# Power.net
KiCad netlist of a schematic drawn in Altium Designer
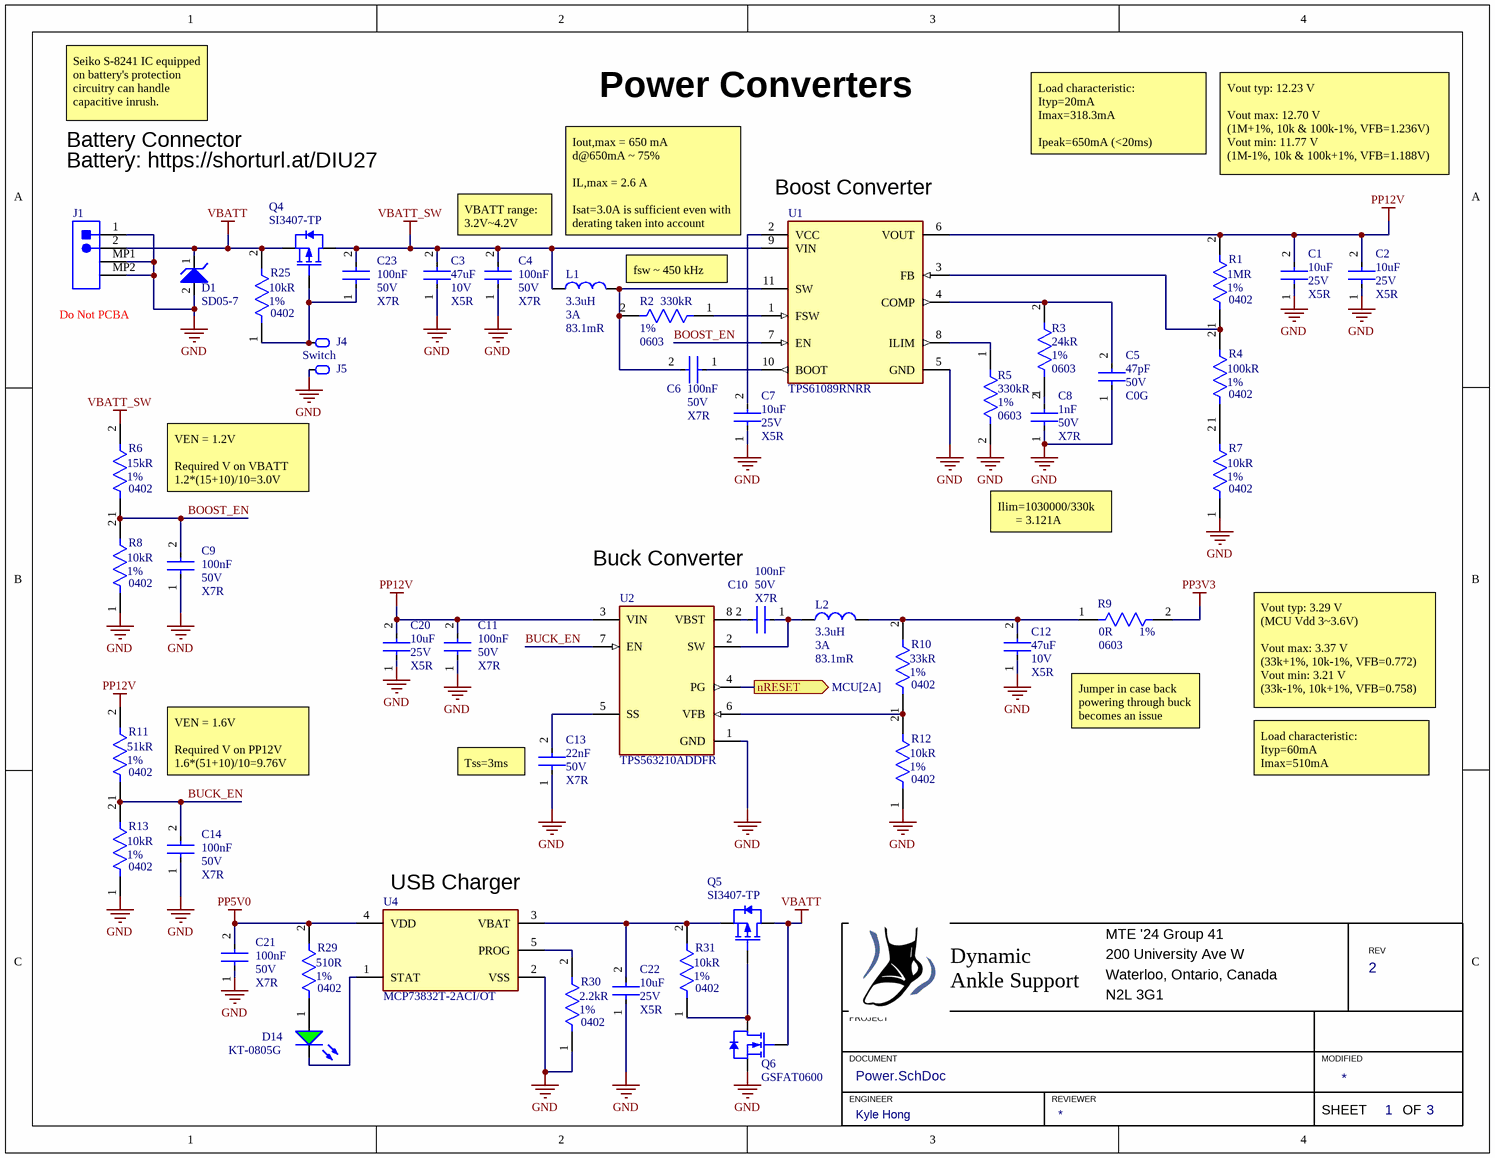
[diagram p0: Power.SchDoc]

(export (version "E")
  (design (tool "Eeschema 10.0.6"))
  (components
    (comp (ref "C1")
      (value "CL21A106KAYNNNE")
      (footprint "CAP0805")
      (description "25V 10uF X5R ±10% 0805  Multilayer Ceramic Capacitors MLCC - SMD/SMT ROHS")
      (fields
        (field (name "TOLERANCE") "10%")
        (field (name "MANUFACTURER") "Samsung Electro-Mechanics")
        (field (name "DIELECTRIC") "X5R")
        (field (name "VOLTAGE RATING") "25V")
        (field (name "CAPACITANCE") "10uF")
      )
      (libsource (lib "FYDP_library_sch") (part "CAP0805"))
    )
    (comp (ref "C2")
      (value "CL21A106KAYNNNE")
      (footprint "CAP0805")
      (description "25V 10uF X5R ±10% 0805  Multilayer Ceramic Capacitors MLCC - SMD/SMT ROHS")
      (fields
        (field (name "TOLERANCE") "10%")
        (field (name "MANUFACTURER") "Samsung Electro-Mechanics")
        (field (name "DIELECTRIC") "X5R")
        (field (name "VOLTAGE RATING") "25V")
        (field (name "CAPACITANCE") "10uF")
      )
      (libsource (lib "FYDP_library_sch") (part "CAP0805"))
    )
    (comp (ref "C3")
      (value "CL31A476MPHNNNE")
      (footprint "CAP1206")
      (description "10V 47uF X5R ±20% 1206  Multilayer Ceramic Capacitors MLCC - SMD/SMT ROHS")
      (fields
        (field (name "TOLERANCE") "20%")
        (field (name "MANUFACTURER") "Samsung Electro-Mechanics")
        (field (name "DIELECTRIC") "X5R")
        (field (name "VOLTAGE RATING") "10V")
        (field (name "CAPACITANCE") "47uF")
      )
      (libsource (lib "FYDP_library_sch") (part "CAP1206"))
    )
    (comp (ref "C4")
      (value "CL05B104KB54PNC")
      (footprint "CAP0402")
      (description "50V 100nF X7R ±10% 0402  Multilayer Ceramic Capacitors MLCC - SMD/SMT ROHS")
      (fields
        (field (name "TOLERANCE") "±20%")
        (field (name "MANUFACTURER") "Samsung Electro-Mechanics")
        (field (name "DIELECTRIC") "X7R")
        (field (name "VOLTAGE RATING") "50V")
        (field (name "CAPACITANCE") "100nF")
      )
      (libsource (lib "FYDP_library_sch") (part "CAP0402"))
    )
    (comp (ref "C5")
      (value "0402CG470J500NT")
      (footprint "CAP0402")
      (description "50V 47pF C0G ±5% 0402  Multilayer Ceramic Capacitors MLCC - SMD/SMT ROHS")
      (fields
        (field (name "TOLERANCE") "±5%")
        (field (name "MANUFACTURER") "FH (Guangdong Fenghua Advanced Tech)")
        (field (name "DIELECTRIC") "C0G")
        (field (name "VOLTAGE RATING") "50V")
        (field (name "CAPACITANCE") "47pF")
      )
      (libsource (lib "FYDP_library_sch") (part "CAP0402"))
    )
    (comp (ref "C6")
      (value "CL05B104KB54PNC")
      (footprint "CAP0402")
      (description "50V 100nF X7R ±10% 0402  Multilayer Ceramic Capacitors MLCC - SMD/SMT ROHS")
      (fields
        (field (name "TOLERANCE") "±20%")
        (field (name "MANUFACTURER") "Samsung Electro-Mechanics")
        (field (name "DIELECTRIC") "X7R")
        (field (name "VOLTAGE RATING") "50V")
        (field (name "CAPACITANCE") "100nF")
      )
      (libsource (lib "FYDP_library_sch") (part "CAP0402"))
    )
    (comp (ref "C7")
      (value "CL21A106KAYNNNE")
      (footprint "CAP0805")
      (description "25V 10uF X5R ±10% 0805  Multilayer Ceramic Capacitors MLCC - SMD/SMT ROHS")
      (fields
        (field (name "TOLERANCE") "10%")
        (field (name "MANUFACTURER") "Samsung Electro-Mechanics")
        (field (name "DIELECTRIC") "X5R")
        (field (name "VOLTAGE RATING") "25V")
        (field (name "CAPACITANCE") "10uF")
      )
      (libsource (lib "FYDP_library_sch") (part "CAP0805"))
    )
    (comp (ref "C8")
      (value "0402B102K500NT")
      (footprint "CAP0402")
      (description "50V 1nF X7R ±10% 0402  Multilayer Ceramic Capacitors MLCC - SMD/SMT ROHS")
      (fields
        (field (name "TOLERANCE") "±10%")
        (field (name "MANUFACTURER") "FH (Guangdong Fenghua Advanced Tech)")
        (field (name "DIELECTRIC") "X7R")
        (field (name "VOLTAGE RATING") "50V")
        (field (name "CAPACITANCE") "1nF")
      )
      (libsource (lib "FYDP_library_sch") (part "CAP0402"))
    )
    (comp (ref "C9")
      (value "CL05B104KB54PNC")
      (footprint "CAP0402")
      (description "50V 100nF X7R ±10% 0402  Multilayer Ceramic Capacitors MLCC - SMD/SMT ROHS")
      (fields
        (field (name "TOLERANCE") "±20%")
        (field (name "MANUFACTURER") "Samsung Electro-Mechanics")
        (field (name "DIELECTRIC") "X7R")
        (field (name "VOLTAGE RATING") "50V")
        (field (name "CAPACITANCE") "100nF")
      )
      (libsource (lib "FYDP_library_sch") (part "CAP0402"))
    )
    (comp (ref "C10")
      (value "CL05B104KB54PNC")
      (footprint "CAP0402")
      (description "50V 100nF X7R ±10% 0402  Multilayer Ceramic Capacitors MLCC - SMD/SMT ROHS")
      (fields
        (field (name "TOLERANCE") "±20%")
        (field (name "MANUFACTURER") "Samsung Electro-Mechanics")
        (field (name "DIELECTRIC") "X7R")
        (field (name "VOLTAGE RATING") "50V")
        (field (name "CAPACITANCE") "100nF")
      )
      (libsource (lib "FYDP_library_sch") (part "CAP0402"))
    )
    (comp (ref "C11")
      (value "CL05B104KB54PNC")
      (footprint "CAP0402")
      (description "50V 100nF X7R ±10% 0402  Multilayer Ceramic Capacitors MLCC - SMD/SMT ROHS")
      (fields
        (field (name "TOLERANCE") "±20%")
        (field (name "MANUFACTURER") "Samsung Electro-Mechanics")
        (field (name "DIELECTRIC") "X7R")
        (field (name "VOLTAGE RATING") "50V")
        (field (name "CAPACITANCE") "100nF")
      )
      (libsource (lib "FYDP_library_sch") (part "CAP0402"))
    )
    (comp (ref "C12")
      (value "CL31A476MPHNNNE")
      (footprint "CAP1206")
      (description "10V 47uF X5R ±20% 1206  Multilayer Ceramic Capacitors MLCC - SMD/SMT ROHS")
      (fields
        (field (name "TOLERANCE") "20%")
        (field (name "MANUFACTURER") "Samsung Electro-Mechanics")
        (field (name "DIELECTRIC") "X5R")
        (field (name "VOLTAGE RATING") "10V")
        (field (name "CAPACITANCE") "47uF")
      )
      (libsource (lib "FYDP_library_sch") (part "CAP1206"))
    )
    (comp (ref "C13")
      (value "0402B223K500NT")
      (footprint "CAP0402")
      (description "50V 22nF X7R ±10% 0402  Multilayer Ceramic Capacitors MLCC - SMD/SMT ROHS")
      (fields
        (field (name "TOLERANCE") "10%")
        (field (name "MANUFACTURER") "FH (Guangdong Fenghua Advanced Tech)")
        (field (name "DIELECTRIC") "X7R")
        (field (name "VOLTAGE RATING") "50V")
        (field (name "CAPACITANCE") "22nF")
      )
      (libsource (lib "FYDP_library_sch") (part "CAP0402"))
    )
    (comp (ref "C14")
      (value "CL05B104KB54PNC")
      (footprint "CAP0402")
      (description "50V 100nF X7R ±10% 0402  Multilayer Ceramic Capacitors MLCC - SMD/SMT ROHS")
      (fields
        (field (name "TOLERANCE") "±20%")
        (field (name "MANUFACTURER") "Samsung Electro-Mechanics")
        (field (name "DIELECTRIC") "X7R")
        (field (name "VOLTAGE RATING") "50V")
        (field (name "CAPACITANCE") "100nF")
      )
      (libsource (lib "FYDP_library_sch") (part "CAP0402"))
    )
    (comp (ref "C20")
      (value "CL21A106KAYNNNE")
      (footprint "CAP0805")
      (description "25V 10uF X5R ±10% 0805  Multilayer Ceramic Capacitors MLCC - SMD/SMT ROHS")
      (fields
        (field (name "TOLERANCE") "10%")
        (field (name "MANUFACTURER") "Samsung Electro-Mechanics")
        (field (name "DIELECTRIC") "X5R")
        (field (name "VOLTAGE RATING") "25V")
        (field (name "CAPACITANCE") "10uF")
      )
      (libsource (lib "FYDP_library_sch") (part "CAP0805"))
    )
    (comp (ref "C21")
      (value "CL05B104KB54PNC")
      (footprint "CAP0402")
      (description "50V 100nF X7R ±10% 0402  Multilayer Ceramic Capacitors MLCC - SMD/SMT ROHS")
      (fields
        (field (name "TOLERANCE") "±20%")
        (field (name "MANUFACTURER") "Samsung Electro-Mechanics")
        (field (name "DIELECTRIC") "X7R")
        (field (name "VOLTAGE RATING") "50V")
        (field (name "CAPACITANCE") "100nF")
      )
      (libsource (lib "FYDP_library_sch") (part "CAP0402"))
    )
    (comp (ref "C22")
      (value "CL21A106KAYNNNE")
      (footprint "CAP0805")
      (description "25V 10uF X5R ±10% 0805  Multilayer Ceramic Capacitors MLCC - SMD/SMT ROHS")
      (fields
        (field (name "TOLERANCE") "10%")
        (field (name "MANUFACTURER") "Samsung Electro-Mechanics")
        (field (name "DIELECTRIC") "X5R")
        (field (name "VOLTAGE RATING") "25V")
        (field (name "CAPACITANCE") "10uF")
      )
      (libsource (lib "FYDP_library_sch") (part "CAP0805"))
    )
    (comp (ref "C23")
      (value "CL05B104KB54PNC")
      (footprint "CAP0402")
      (description "50V 100nF X7R ±10% 0402  Multilayer Ceramic Capacitors MLCC - SMD/SMT ROHS")
      (fields
        (field (name "TOLERANCE") "±20%")
        (field (name "MANUFACTURER") "Samsung Electro-Mechanics")
        (field (name "DIELECTRIC") "X7R")
        (field (name "VOLTAGE RATING") "50V")
        (field (name "CAPACITANCE") "100nF")
      )
      (libsource (lib "FYDP_library_sch") (part "CAP0402"))
    )
    (comp (ref "D1")
      (value "SD05-7")
      (footprint "SD05-7")
      (description "TVS UNI14.5V 6.2V 5V SOD-323")
      (fields (field (name "MANUFACTURER") "Diodes Incorporated"))
      (libsource (lib "FYDP_library_sch") (part "SD05-7"))
    )
    (comp (ref "D14")
      (value "KT-0805G")
      (footprint "LED_0805_GREEN")
      (description "Emerald 0805  Light Emitting Diodes (LED) ROHS")
      (fields (field (name "MANUFACTURER") "Hubei KENTO Elec"))
      (libsource (lib "FYDP_library_sch") (part "LED_GREEN"))
    )
    (comp (ref "J1")
      (value "S2B-PH-SM4-TB(LF)(SN)")
      (footprint "JST- S2B-PH-SM4-TB(LF)(SN)-2_V")
      (description "Male Header, Pitch 2 mm, 1 x 2 Position, Height 5.5 mm, -25 to 85 degC, RoHS, Tape and Reel")
      (libsource (lib "Altium Content Vault") (part "CN-1P-2M-R2"))
    )
    (comp (ref "J4")
      (value "SOLDER_PAD")
      (footprint "SOLDER_PAD")
      (libsource (lib "FYDP_library_sch") (part "SOLDER_PAD"))
    )
    (comp (ref "J5")
      (value "SOLDER_PAD")
      (footprint "SOLDER_PAD")
      (libsource (lib "FYDP_library_sch") (part "SOLDER_PAD"))
    )
    (comp (ref "L1")
      (value "IHLP1616BZER3R3M5A")
      (footprint "TMPA0503S-3R3MN-D")
      (description "3.3uH ±20% 3A SMD Power Inductors ROHS")
      (fields
        (field (name "MANUFACTURER") "Vishay Intertech")
        (field (name "TOLERANCE") "20%")
        (field (name "DC RESISTANCE") "83.1mR")
        (field (name "ISAT(MIN)") "3A")
        (field (name "INDUCTANCE") "3.3uH")
      )
      (libsource (lib "FYDP_library_sch") (part "TMPA0503S-3R3MN-D"))
    )
    (comp (ref "L2")
      (value "IHLP1616BZER3R3M5A")
      (footprint "TMPA0503S-3R3MN-D")
      (description "3.3uH ±20% 3A SMD Power Inductors ROHS")
      (fields
        (field (name "MANUFACTURER") "Vishay Intertech")
        (field (name "TOLERANCE") "20%")
        (field (name "DC RESISTANCE") "83.1mR")
        (field (name "ISAT(MIN)") "3A")
        (field (name "INDUCTANCE") "3.3uH")
      )
      (libsource (lib "FYDP_library_sch") (part "TMPA0503S-3R3MN-D"))
    )
    (comp (ref "Q4")
      (value "SI3407-TP")
      (footprint "SOT23-3")
      (description "MOSFET P-CH 30V 4.1A SOT23")
      (libsource (lib "FYDP_library_sch") (part "IRLML5103TRPBF"))
    )
    (comp (ref "Q5")
      (value "SI3407-TP")
      (footprint "SOT23-3")
      (description "MOSFET P-CH 30V 4.1A SOT23")
      (libsource (lib "FYDP_library_sch") (part "IRLML5103TRPBF"))
    )
    (comp (ref "Q6")
      (value "GSFAT0600")
      (footprint "SOT-523")
      (description "MOSFET, N-CH, SINGLE, 0.30A, 60V")
      (libsource (lib "FYDP_library_sch") (part "DMN62D0UT-7"))
    )
    (comp (ref "R1")
      (value "0402WGF1004TCE")
      (footprint "RES0402")
      (description "62.5mW Thick Film Resistors ±100ppm/℃ ±1% 1MΩ 0402  Chip Resistor - Surface Mount ROHS")
      (fields
        (field (name "MANUFACTURER") "UNI-ROYAL(Uniroyal Elec)")
        (field (name "TOLERANCE") "1%")
        (field (name "RESISTANCE") "1MR")
        (field (name "PACKAGE") "0402")
      )
      (libsource (lib "FYDP_library_sch") (part "RES0402"))
    )
    (comp (ref "R2")
      (value "0603WAF3303T5E")
      (footprint "RES0603")
      (description "100mW Thick Film Resistors ±100ppm/℃ ±1% 330kΩ 0603  Chip Resistor - Surface Mount ROHS")
      (fields
        (field (name "MANUFACTURER") "UNI-ROYAL(Uniroyal Elec)")
        (field (name "TOLERANCE") "1%")
        (field (name "RESISTANCE") "330kR")
        (field (name "PACKAGE") "0603")
      )
      (libsource (lib "FYDP_library_sch") (part "RES0603"))
    )
    (comp (ref "R3")
      (value "0603WAF2402T5E")
      (footprint "RES0603")
      (description "100mW Thick Film Resistors ±100ppm/℃ ±1% 24kΩ 0603  Chip Resistor - Surface Mount ROHS")
      (fields
        (field (name "MANUFACTURER") "UNI-ROYAL(Uniroyal Elec)")
        (field (name "TOLERANCE") "1%")
        (field (name "RESISTANCE") "24kR")
        (field (name "PACKAGE") "0603")
      )
      (libsource (lib "FYDP_library_sch") (part "RES0603"))
    )
    (comp (ref "R4")
      (value "0402WGF1003TCE")
      (footprint "RES0402")
      (description "62.5mW Thick Film Resistors ±100ppm/℃ ±1% 100kΩ 0402  Chip Resistor - Surface Mount ROHS")
      (fields
        (field (name "MANUFACTURER") "UNI-ROYAL(Uniroyal Elec)")
        (field (name "TOLERANCE") "1%")
        (field (name "RESISTANCE") "100kR")
        (field (name "PACKAGE") "0402")
      )
      (libsource (lib "FYDP_library_sch") (part "RES0402"))
    )
    (comp (ref "R5")
      (value "0603WAF3303T5E")
      (footprint "RES0603")
      (description "100mW Thick Film Resistors ±100ppm/℃ ±1% 330kΩ 0603  Chip Resistor - Surface Mount ROHS")
      (fields
        (field (name "MANUFACTURER") "UNI-ROYAL(Uniroyal Elec)")
        (field (name "TOLERANCE") "1%")
        (field (name "RESISTANCE") "330kR")
        (field (name "PACKAGE") "0603")
      )
      (libsource (lib "FYDP_library_sch") (part "RES0603"))
    )
    (comp (ref "R6")
      (value "0402WGF1502TCE")
      (footprint "RES0402")
      (description "62.5mW Thick Film Resistors ±100ppm/℃ ±1% 15kΩ 0402  Chip Resistor - Surface Mount ROHS")
      (fields
        (field (name "MANUFACTURER") "UNI-ROYAL(Uniroyal Elec)")
        (field (name "TOLERANCE") "1%")
        (field (name "RESISTANCE") "15kR")
        (field (name "PACKAGE") "0402")
      )
      (libsource (lib "FYDP_library_sch") (part "RES0402"))
    )
    (comp (ref "R7")
      (value "0402WGF1002TCE")
      (footprint "RES0402")
      (description "62.5mW Thick Film Resistors ±100ppm/℃ ±1% 10kΩ 0402  Chip Resistor - Surface Mount ROHS")
      (fields
        (field (name "MANUFACTURER") "UNI-ROYAL(Uniroyal Elec)")
        (field (name "TOLERANCE") "1%")
        (field (name "RESISTANCE") "10kR")
        (field (name "PACKAGE") "0402")
      )
      (libsource (lib "FYDP_library_sch") (part "RES0402"))
    )
    (comp (ref "R8")
      (value "0402WGF1002TCE")
      (footprint "RES0402")
      (description "62.5mW Thick Film Resistors ±100ppm/℃ ±1% 10kΩ 0402  Chip Resistor - Surface Mount ROHS")
      (fields
        (field (name "MANUFACTURER") "UNI-ROYAL(Uniroyal Elec)")
        (field (name "TOLERANCE") "1%")
        (field (name "RESISTANCE") "10kR")
        (field (name "PACKAGE") "0402")
      )
      (libsource (lib "FYDP_library_sch") (part "RES0402"))
    )
    (comp (ref "R9")
      (value "0603WAF0000T5E")
      (footprint "RES0603")
      (description "100mW Thick Film Resistors ±1% 0Ω 0603  Chip Resistor - Surface Mount ROHS")
      (fields
        (field (name "MANUFACTURER") "UNI-ROYAL(Uniroyal Elec)")
        (field (name "TOLERANCE") "1%")
        (field (name "RESISTANCE") "0R")
        (field (name "PACKAGE") "0603")
      )
      (libsource (lib "FYDP_library_sch") (part "RES0603"))
    )
    (comp (ref "R10")
      (value "0402WGF3302TCE")
      (footprint "RES0402")
      (description "62.5mW Thick Film Resistors ±100ppm/℃ ±1% 33kΩ 0402  Chip Resistor - Surface Mount ROHS")
      (fields
        (field (name "MANUFACTURER") "UNI-ROYAL(Uniroyal Elec)")
        (field (name "TOLERANCE") "1%")
        (field (name "RESISTANCE") "33kR")
        (field (name "PACKAGE") "0402")
      )
      (libsource (lib "FYDP_library_sch") (part "RES0402"))
    )
    (comp (ref "R11")
      (value "0402WGF5102TCE")
      (footprint "RES0402")
      (description "62.5mW Thick Film Resistors ±100ppm/℃ ±1% 51kΩ 0402  Chip Resistor - Surface Mount ROHS")
      (fields
        (field (name "MANUFACTURER") "UNI-ROYAL(Uniroyal Elec)")
        (field (name "TOLERANCE") "1%")
        (field (name "RESISTANCE") "51kR")
        (field (name "PACKAGE") "0402")
      )
      (libsource (lib "FYDP_library_sch") (part "RES0402"))
    )
    (comp (ref "R12")
      (value "0402WGF1002TCE")
      (footprint "RES0402")
      (description "62.5mW Thick Film Resistors ±100ppm/℃ ±1% 10kΩ 0402  Chip Resistor - Surface Mount ROHS")
      (fields
        (field (name "MANUFACTURER") "UNI-ROYAL(Uniroyal Elec)")
        (field (name "TOLERANCE") "1%")
        (field (name "RESISTANCE") "10kR")
        (field (name "PACKAGE") "0402")
      )
      (libsource (lib "FYDP_library_sch") (part "RES0402"))
    )
    (comp (ref "R13")
      (value "0402WGF1002TCE")
      (footprint "RES0402")
      (description "62.5mW Thick Film Resistors ±100ppm/℃ ±1% 10kΩ 0402  Chip Resistor - Surface Mount ROHS")
      (fields
        (field (name "MANUFACTURER") "UNI-ROYAL(Uniroyal Elec)")
        (field (name "TOLERANCE") "1%")
        (field (name "RESISTANCE") "10kR")
        (field (name "PACKAGE") "0402")
      )
      (libsource (lib "FYDP_library_sch") (part "RES0402"))
    )
    (comp (ref "R25")
      (value "0402WGF1002TCE")
      (footprint "RES0402")
      (description "62.5mW Thick Film Resistors ±100ppm/℃ ±1% 10kΩ 0402  Chip Resistor - Surface Mount ROHS")
      (fields
        (field (name "MANUFACTURER") "UNI-ROYAL(Uniroyal Elec)")
        (field (name "TOLERANCE") "1%")
        (field (name "RESISTANCE") "10kR")
        (field (name "PACKAGE") "0402")
      )
      (libsource (lib "FYDP_library_sch") (part "RES0402"))
    )
    (comp (ref "R29")
      (value "0402WGF5100TCE")
      (footprint "RES0402")
      (description "62.5mW Thick Film Resistors ±100ppm/℃ ±1% 510Ω 0402  Chip Resistor - Surface Mount ROHS")
      (fields
        (field (name "MANUFACTURER") "UNI-ROYAL(Uniroyal Elec)")
        (field (name "TOLERANCE") "1%")
        (field (name "RESISTANCE") "510R")
        (field (name "PACKAGE") "0402")
      )
      (libsource (lib "FYDP_library_sch") (part "RES0402"))
    )
    (comp (ref "R30")
      (value "0402WGF2201TCE")
      (footprint "RES0402")
      (description "62.5mW Thick Film Resistors ±100ppm/℃ ±1% 2.2kΩ 0402  Chip Resistor - Surface Mount ROHS")
      (fields
        (field (name "MANUFACTURER") "UNI-ROYAL(Uniroyal Elec)")
        (field (name "TOLERANCE") "1%")
        (field (name "RESISTANCE") "2.2kR")
        (field (name "PACKAGE") "0402")
      )
      (libsource (lib "FYDP_library_sch") (part "RES0402"))
    )
    (comp (ref "R31")
      (value "0402WGF1002TCE")
      (footprint "RES0402")
      (description "62.5mW Thick Film Resistors ±100ppm/℃ ±1% 10kΩ 0402  Chip Resistor - Surface Mount ROHS")
      (fields
        (field (name "MANUFACTURER") "UNI-ROYAL(Uniroyal Elec)")
        (field (name "TOLERANCE") "1%")
        (field (name "RESISTANCE") "10kR")
        (field (name "PACKAGE") "0402")
      )
      (libsource (lib "FYDP_library_sch") (part "RES0402"))
    )
    (comp (ref "U1")
      (value "TPS61089RNRR")
      (footprint "FP-RNR0011A-MFG")
      (description "IC REG BOOST ADJ 7A 11VQFN")
      (fields
        (field (name "MANUFACTURER") "Texas Instruments")
        (field (name "OCTOPART") "https://octopart.com/tps61089rnrr-texas+instruments-68059594")
      )
      (libsource (lib "Altium Content Vault") (part "a261192ae58a3958df181bc9456d026"))
    )
    (comp (ref "U2")
      (value "TPS563210ADDFR")
      (footprint "TPS563210ADDFR")
      (description "IC REG BUCK ADJ 3A SOT-23-8")
      (fields (field (name "MANUFACTURER") "Texas Instruments"))
      (libsource (lib "FYDP_library_sch") (part "TPS563210ADDFR"))
    )
    (comp (ref "U4")
      (value "MCP73832T-2ACI/OT")
      (footprint "FP-C04-091-OT-MFG")
      (description "IC LI-ION/LI-POLY CTRLR SOT23-5")
      (libsource (lib "Altium Content Vault") (part "61f5a3bb3429d9e0caadea342aa3b19"))
    )
  )
  (nets
    (net (code "1") (name "/BOOST_EN") (class "Default")
      (node (ref "C9") (pin "2") (pinfunction "2_2") (pintype "passive"))
      (node (ref "R6") (pin "1") (pinfunction "1_1") (pintype "passive"))
      (node (ref "R8") (pin "2") (pinfunction "2_2") (pintype "passive"))
      (node (ref "U1") (pin "7") (pinfunction "EN_7") (pintype "input"))
    )
    (net (code "2") (name "/BUCK_EN") (class "Default")
      (node (ref "C14") (pin "2") (pinfunction "2_2") (pintype "passive"))
      (node (ref "R11") (pin "1") (pinfunction "1_1") (pintype "passive"))
      (node (ref "R13") (pin "2") (pinfunction "2_2") (pintype "passive"))
      (node (ref "U2") (pin "7") (pinfunction "EN_7") (pintype "input"))
    )
    (net (code "3") (name "/nRESET") (class "Default")
      (node (ref "U2") (pin "4") (pinfunction "PG_4") (pintype "output"))
    )
    (net (code "4") (name "GND") (class "Default")
      (node (ref "C1") (pin "1") (pinfunction "1_1") (pintype "passive"))
      (node (ref "C11") (pin "1") (pinfunction "1_1") (pintype "passive"))
      (node (ref "C12") (pin "1") (pinfunction "1_1") (pintype "passive"))
      (node (ref "C13") (pin "1") (pinfunction "1_1") (pintype "passive"))
      (node (ref "C14") (pin "1") (pinfunction "1_1") (pintype "passive"))
      (node (ref "C2") (pin "1") (pinfunction "1_1") (pintype "passive"))
      (node (ref "C20") (pin "1") (pinfunction "1_1") (pintype "passive"))
      (node (ref "C21") (pin "1") (pinfunction "1_1") (pintype "passive"))
      (node (ref "C22") (pin "1") (pinfunction "1_1") (pintype "passive"))
      (node (ref "C3") (pin "1") (pinfunction "1_1") (pintype "passive"))
      (node (ref "C4") (pin "1") (pinfunction "1_1") (pintype "passive"))
      (node (ref "C5") (pin "1") (pinfunction "1_1") (pintype "passive"))
      (node (ref "C7") (pin "1") (pinfunction "1_1") (pintype "passive"))
      (node (ref "C8") (pin "1") (pinfunction "1_1") (pintype "passive"))
      (node (ref "C9") (pin "1") (pinfunction "1_1") (pintype "passive"))
      (node (ref "D1") (pin "2") (pinfunction "2_2") (pintype "passive"))
      (node (ref "J1") (pin "1") (pinfunction "1_1") (pintype "passive"))
      (node (ref "J1") (pin "MP1") (pinfunction "MP1_MP1") (pintype "passive"))
      (node (ref "J1") (pin "MP2") (pinfunction "MP2_MP2") (pintype "passive"))
      (node (ref "J5") (pin "1") (pinfunction "1_1") (pintype "passive"))
      (node (ref "Q6") (pin "2") (pinfunction "SOURCE_2") (pintype "passive"))
      (node (ref "R12") (pin "1") (pinfunction "1_1") (pintype "passive"))
      (node (ref "R13") (pin "1") (pinfunction "1_1") (pintype "passive"))
      (node (ref "R30") (pin "1") (pinfunction "1_1") (pintype "passive"))
      (node (ref "R5") (pin "2") (pinfunction "2_2") (pintype "passive"))
      (node (ref "R7") (pin "1") (pinfunction "1_1") (pintype "passive"))
      (node (ref "R8") (pin "1") (pinfunction "1_1") (pintype "passive"))
      (node (ref "U1") (pin "5") (pinfunction "GND_5") (pintype "power_in"))
      (node (ref "U2") (pin "1") (pinfunction "GND_1") (pintype "passive"))
      (node (ref "U4") (pin "2") (pinfunction "VSS_2") (pintype "power_in"))
    )
    (net (code "5") (name "Net-(C8-Pad2)") (class "Default")
      (node (ref "C8") (pin "2") (pinfunction "2_2") (pintype "passive"))
      (node (ref "R3") (pin "1") (pinfunction "1_1") (pintype "passive"))
    )
    (net (code "6") (name "Net-(C12-Pad2)") (class "Default")
      (node (ref "C12") (pin "2") (pinfunction "2_2") (pintype "passive"))
      (node (ref "L2") (pin "2") (pinfunction "2_2") (pintype "passive"))
      (node (ref "R10") (pin "2") (pinfunction "2_2") (pintype "passive"))
      (node (ref "R9") (pin "1") (pinfunction "1_1") (pintype "passive"))
    )
    (net (code "7") (name "Net-(D14-A)") (class "Default")
      (node (ref "D14") (pin "2") (pinfunction "A_2") (pintype "passive"))
      (node (ref "R29") (pin "1") (pinfunction "1_1") (pintype "passive"))
    )
    (net (code "8") (name "Net-(D14-K)") (class "Default")
      (node (ref "D14") (pin "1") (pinfunction "K_1") (pintype "passive"))
      (node (ref "U4") (pin "1") (pinfunction "STAT_1") (pintype "passive"))
    )
    (net (code "9") (name "Net-(Q4-Gate)") (class "Default")
      (node (ref "C23") (pin "1") (pinfunction "1_1") (pintype "passive"))
      (node (ref "J4") (pin "1") (pinfunction "1_1") (pintype "passive"))
      (node (ref "Q4") (pin "1") (pinfunction "Gate_1") (pintype "passive"))
      (node (ref "R25") (pin "1") (pinfunction "1_1") (pintype "passive"))
    )
    (net (code "10") (name "Net-(Q5-Gate)") (class "Default")
      (node (ref "Q5") (pin "1") (pinfunction "Gate_1") (pintype "passive"))
      (node (ref "Q6") (pin "3") (pinfunction "DRAIN_3") (pintype "passive"))
      (node (ref "R31") (pin "1") (pinfunction "1_1") (pintype "passive"))
    )
    (net (code "11") (name "Net-(Q5-Source)") (class "Default")
      (node (ref "C22") (pin "2") (pinfunction "2_2") (pintype "passive"))
      (node (ref "Q5") (pin "2") (pinfunction "Source_2") (pintype "passive"))
      (node (ref "R31") (pin "2") (pinfunction "2_2") (pintype "passive"))
      (node (ref "U4") (pin "3") (pinfunction "VBAT_3") (pintype "power_in"))
    )
    (net (code "12") (name "Net-(R4-Pad1)") (class "Default")
      (node (ref "R4") (pin "1") (pinfunction "1_1") (pintype "passive"))
      (node (ref "R7") (pin "2") (pinfunction "2_2") (pintype "passive"))
    )
    (net (code "13") (name "Net-(U1-BOOT)") (class "Default")
      (node (ref "C6") (pin "1") (pinfunction "1_1") (pintype "passive"))
      (node (ref "U1") (pin "10") (pinfunction "BOOT_10") (pintype "output"))
    )
    (net (code "14") (name "Net-(U1-COMP)") (class "Default")
      (node (ref "C5") (pin "2") (pinfunction "2_2") (pintype "passive"))
      (node (ref "R3") (pin "2") (pinfunction "2_2") (pintype "passive"))
      (node (ref "U1") (pin "4") (pinfunction "COMP_4") (pintype "output"))
    )
    (net (code "15") (name "Net-(U1-FB)") (class "Default")
      (node (ref "R1") (pin "1") (pinfunction "1_1") (pintype "passive"))
      (node (ref "R4") (pin "2") (pinfunction "2_2") (pintype "passive"))
      (node (ref "U1") (pin "3") (pinfunction "FB_3") (pintype "input"))
    )
    (net (code "16") (name "Net-(U1-FSW)") (class "Default")
      (node (ref "R2") (pin "1") (pinfunction "1_1") (pintype "passive"))
      (node (ref "U1") (pin "1") (pinfunction "FSW_1") (pintype "input"))
    )
    (net (code "17") (name "Net-(U1-ILIM)") (class "Default")
      (node (ref "R5") (pin "1") (pinfunction "1_1") (pintype "passive"))
      (node (ref "U1") (pin "8") (pinfunction "ILIM_8") (pintype "output"))
    )
    (net (code "18") (name "Net-(U1-SW)") (class "Default")
      (node (ref "C6") (pin "2") (pinfunction "2_2") (pintype "passive"))
      (node (ref "L1") (pin "2") (pinfunction "2_2") (pintype "passive"))
      (node (ref "R2") (pin "2") (pinfunction "2_2") (pintype "passive"))
      (node (ref "U1") (pin "11") (pinfunction "SW_11") (pintype "power_in"))
    )
    (net (code "19") (name "Net-(U1-VCC)") (class "Default")
      (node (ref "C7") (pin "2") (pinfunction "2_2") (pintype "passive"))
      (node (ref "U1") (pin "2") (pinfunction "VCC_2") (pintype "power_in"))
    )
    (net (code "20") (name "Net-(U2-SS)") (class "Default")
      (node (ref "C13") (pin "2") (pinfunction "2_2") (pintype "passive"))
      (node (ref "U2") (pin "5") (pinfunction "SS_5") (pintype "passive"))
    )
    (net (code "21") (name "Net-(U2-SW)") (class "Default")
      (node (ref "C10") (pin "1") (pinfunction "1_1") (pintype "passive"))
      (node (ref "L2") (pin "1") (pinfunction "1_1") (pintype "passive"))
      (node (ref "U2") (pin "2") (pinfunction "SW_2") (pintype "passive"))
    )
    (net (code "22") (name "Net-(U2-VBST)") (class "Default")
      (node (ref "C10") (pin "2") (pinfunction "2_2") (pintype "passive"))
      (node (ref "U2") (pin "8") (pinfunction "VBST_8") (pintype "passive"))
    )
    (net (code "23") (name "Net-(U2-VFB)") (class "Default")
      (node (ref "R10") (pin "1") (pinfunction "1_1") (pintype "passive"))
      (node (ref "R12") (pin "2") (pinfunction "2_2") (pintype "passive"))
      (node (ref "U2") (pin "6") (pinfunction "VFB_6") (pintype "input"))
    )
    (net (code "24") (name "Net-(U4-PROG)") (class "Default")
      (node (ref "R30") (pin "2") (pinfunction "2_2") (pintype "passive"))
      (node (ref "U4") (pin "5") (pinfunction "PROG_5") (pintype "passive"))
    )
    (net (code "25") (name "PP3V3") (class "Default")
      (node (ref "R9") (pin "2") (pinfunction "2_2") (pintype "passive"))
    )
    (net (code "26") (name "PP5V0") (class "Default")
      (node (ref "C21") (pin "2") (pinfunction "2_2") (pintype "passive"))
      (node (ref "R29") (pin "2") (pinfunction "2_2") (pintype "passive"))
      (node (ref "U4") (pin "4") (pinfunction "VDD_4") (pintype "power_in"))
    )
    (net (code "27") (name "PP12V") (class "Default")
      (node (ref "C1") (pin "2") (pinfunction "2_2") (pintype "passive"))
      (node (ref "C11") (pin "2") (pinfunction "2_2") (pintype "passive"))
      (node (ref "C2") (pin "2") (pinfunction "2_2") (pintype "passive"))
      (node (ref "C20") (pin "2") (pinfunction "2_2") (pintype "passive"))
      (node (ref "R1") (pin "2") (pinfunction "2_2") (pintype "passive"))
      (node (ref "R11") (pin "2") (pinfunction "2_2") (pintype "passive"))
      (node (ref "U1") (pin "6") (pinfunction "VOUT_6") (pintype "power_in"))
      (node (ref "U2") (pin "3") (pinfunction "VIN_3") (pintype "passive"))
    )
    (net (code "28") (name "VBATT") (class "Default")
      (node (ref "D1") (pin "1") (pinfunction "1_1") (pintype "passive"))
      (node (ref "J1") (pin "2") (pinfunction "2_2") (pintype "passive"))
      (node (ref "Q4") (pin "2") (pinfunction "Source_2") (pintype "passive"))
      (node (ref "Q5") (pin "3") (pinfunction "Drain_3") (pintype "passive"))
      (node (ref "Q6") (pin "1") (pinfunction "GATE_1") (pintype "passive"))
      (node (ref "R25") (pin "2") (pinfunction "2_2") (pintype "passive"))
    )
    (net (code "29") (name "VBATT_SW") (class "Default")
      (node (ref "C23") (pin "2") (pinfunction "2_2") (pintype "passive"))
      (node (ref "C3") (pin "2") (pinfunction "2_2") (pintype "passive"))
      (node (ref "C4") (pin "2") (pinfunction "2_2") (pintype "passive"))
      (node (ref "L1") (pin "1") (pinfunction "1_1") (pintype "passive"))
      (node (ref "Q4") (pin "3") (pinfunction "Drain_3") (pintype "passive"))
      (node (ref "R6") (pin "2") (pinfunction "2_2") (pintype "passive"))
      (node (ref "U1") (pin "9") (pinfunction "VIN_9") (pintype "power_in"))
    )
  )
)
